# MotorController_ToniDove_Full04.net
KiCad netlist of a schematic drawn in EAGLE
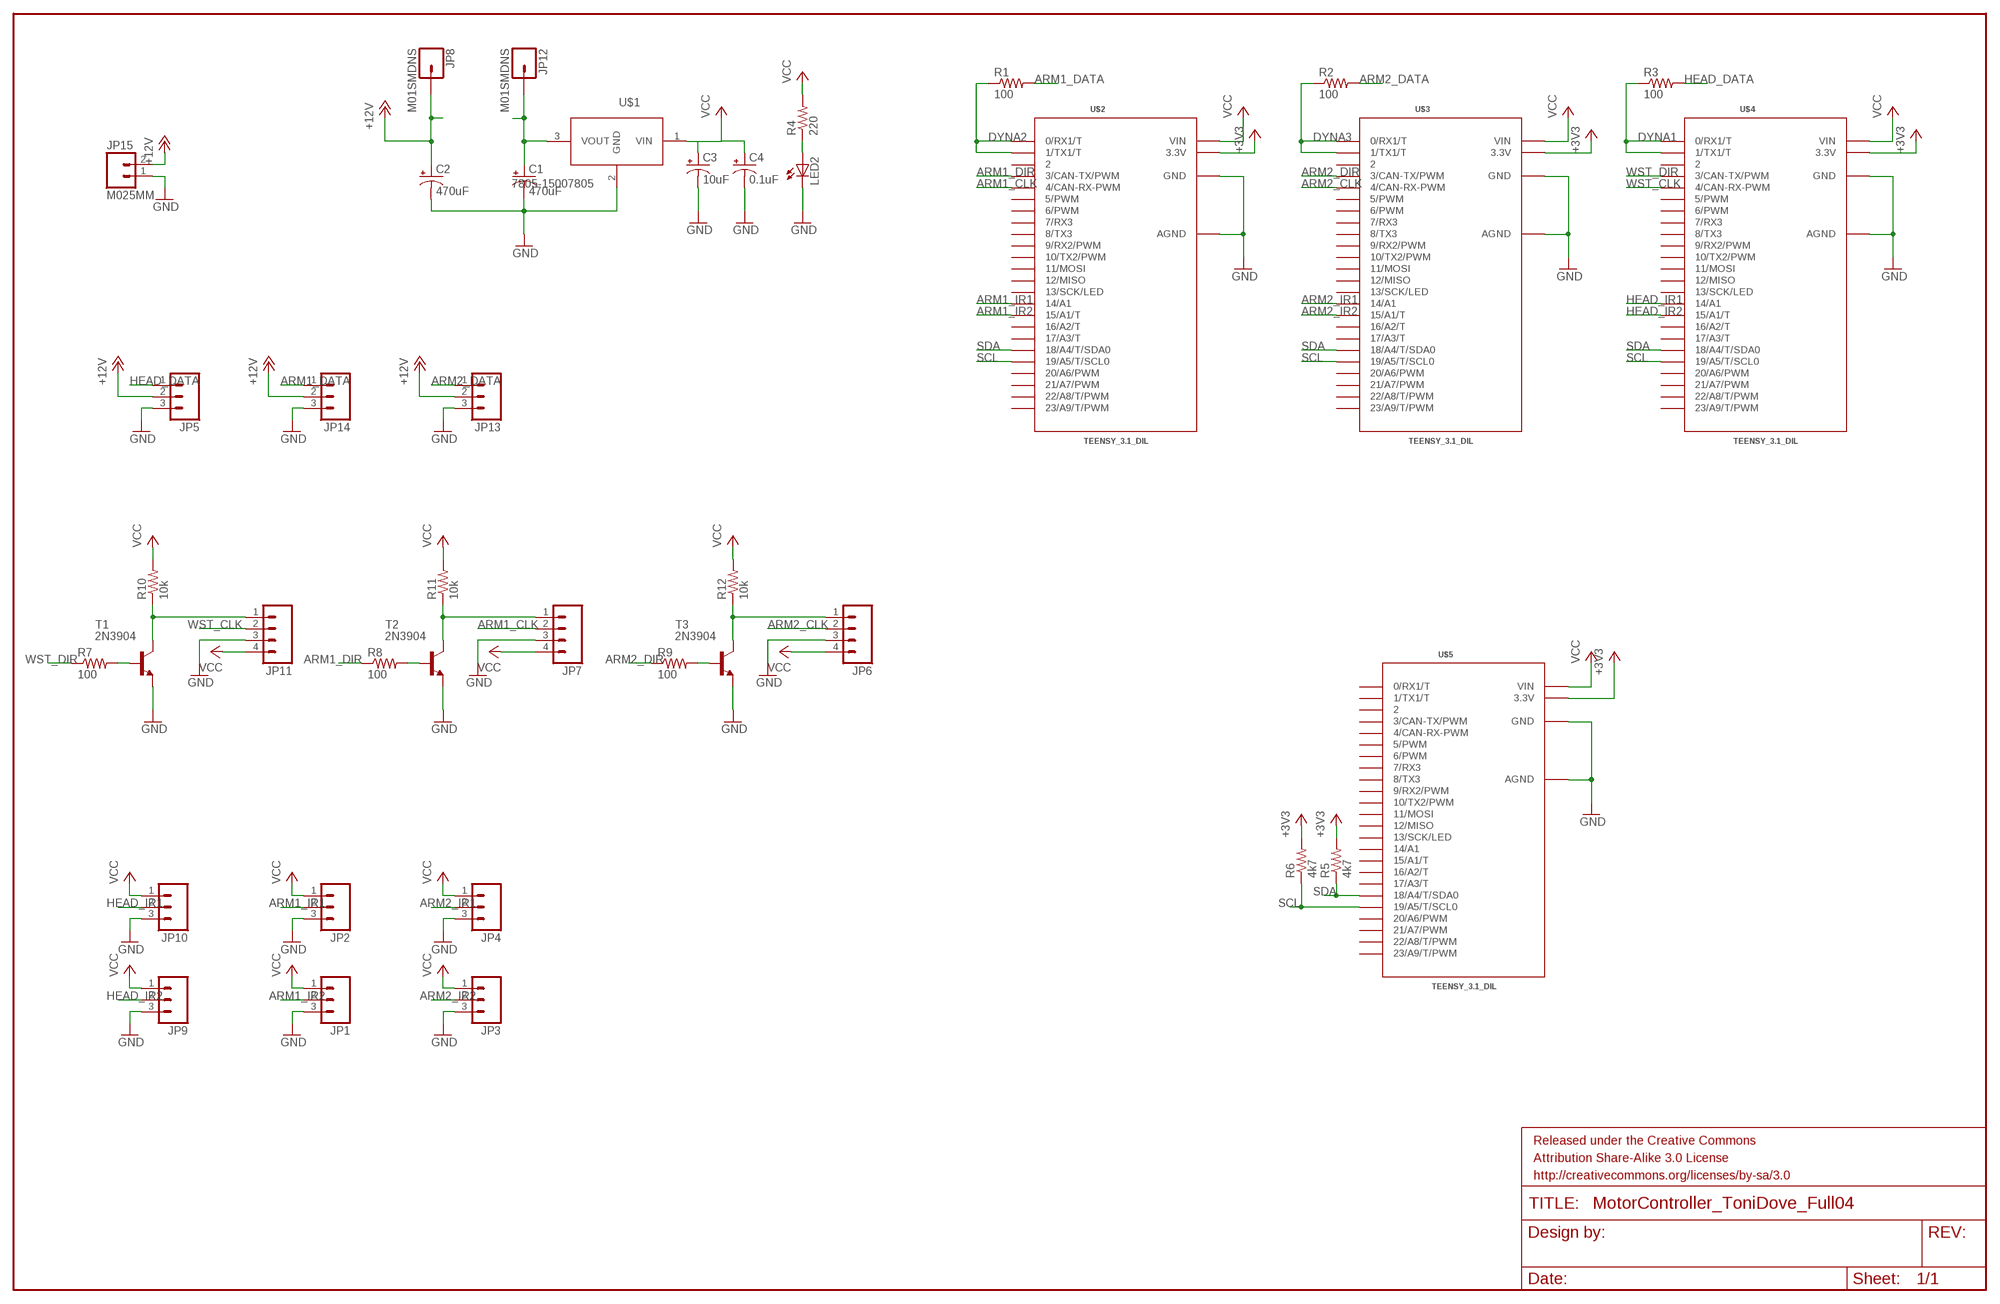
[diagram p0: schematic, sheet 1]

(export (version "E")
  (design (tool "Eeschema 10.0.6"))
  (components
    (comp (ref "C1")
      (value "470uF")
      (footprint "eagle-import:E5-13")
      (libsource (lib "eagle-import") (part "CPOL-USE5-13"))
    )
    (comp (ref "C2")
      (value "470uF")
      (footprint "eagle-import:E5-13")
      (libsource (lib "eagle-import") (part "CPOL-USE5-13"))
    )
    (comp (ref "C3")
      (value "10uF")
      (footprint "eagle-import:E2,5-6E")
      (libsource (lib "eagle-import") (part "CPOL-USE2,5-6E"))
    )
    (comp (ref "C4")
      (value "0.1uF")
      (footprint "eagle-import:E2,5-6E")
      (libsource (lib "eagle-import") (part "CPOL-USE2,5-6E"))
    )
    (comp (ref "FRAME1")
      (value "FRAME-LEDGER")
      (footprint "eagle-import:CREATIVE_COMMONS")
      (libsource (lib "eagle-import") (part "FRAME-LEDGER"))
    )
    (comp (ref "JP1")
      (value "M03PTH")
      (footprint "eagle-import:1X03")
      (libsource (lib "eagle-import") (part "M03PTH"))
    )
    (comp (ref "JP2")
      (value "M03PTH")
      (footprint "eagle-import:1X03")
      (libsource (lib "eagle-import") (part "M03PTH"))
    )
    (comp (ref "JP3")
      (value "M03PTH")
      (footprint "eagle-import:1X03")
      (libsource (lib "eagle-import") (part "M03PTH"))
    )
    (comp (ref "JP4")
      (value "M03PTH")
      (footprint "eagle-import:1X03")
      (libsource (lib "eagle-import") (part "M03PTH"))
    )
    (comp (ref "JP5")
      (value "M03PTH")
      (footprint "eagle-import:1X03")
      (libsource (lib "eagle-import") (part "M03PTH"))
    )
    (comp (ref "JP6")
      (value "M04SCREW")
      (footprint "eagle-import:SCREWTERMINAL-3.5MM-4")
      (libsource (lib "eagle-import") (part "M04SCREW"))
    )
    (comp (ref "JP7")
      (value "M04SCREW")
      (footprint "eagle-import:SCREWTERMINAL-3.5MM-4")
      (libsource (lib "eagle-import") (part "M04SCREW"))
    )
    (comp (ref "JP8")
      (value "M01SMDNS")
      (footprint "eagle-import:1X01NS")
      (libsource (lib "eagle-import") (part "M01SMDNS"))
    )
    (comp (ref "JP9")
      (value "M03PTH")
      (footprint "eagle-import:1X03")
      (libsource (lib "eagle-import") (part "M03PTH"))
    )
    (comp (ref "JP10")
      (value "M03PTH")
      (footprint "eagle-import:1X03")
      (libsource (lib "eagle-import") (part "M03PTH"))
    )
    (comp (ref "JP11")
      (value "M04SCREW")
      (footprint "eagle-import:SCREWTERMINAL-3.5MM-4")
      (libsource (lib "eagle-import") (part "M04SCREW"))
    )
    (comp (ref "JP12")
      (value "M01SMDNS")
      (footprint "eagle-import:1X01NS")
      (libsource (lib "eagle-import") (part "M01SMDNS"))
    )
    (comp (ref "JP13")
      (value "M03PTH")
      (footprint "eagle-import:1X03")
      (libsource (lib "eagle-import") (part "M03PTH"))
    )
    (comp (ref "JP14")
      (value "M03PTH")
      (footprint "eagle-import:1X03")
      (libsource (lib "eagle-import") (part "M03PTH"))
    )
    (comp (ref "JP15")
      (value "M025MM")
      (footprint "eagle-import:SCREWTERMINAL-5MM-2")
      (libsource (lib "eagle-import") (part "M025MM"))
    )
    (comp (ref "LED2")
      (value "LED5MM")
      (footprint "eagle-import:LED5MM")
      (libsource (lib "eagle-import") (part "LED5MM"))
    )
    (comp (ref "R1")
      (value "100")
      (footprint "eagle-import:0204_7")
      (libsource (lib "eagle-import") (part "R-US_0204/7"))
    )
    (comp (ref "R2")
      (value "100")
      (footprint "eagle-import:0204_7")
      (libsource (lib "eagle-import") (part "R-US_0204/7"))
    )
    (comp (ref "R3")
      (value "100")
      (footprint "eagle-import:0204_7")
      (libsource (lib "eagle-import") (part "R-US_0204/7"))
    )
    (comp (ref "R4")
      (value "220")
      (footprint "eagle-import:0204_7")
      (libsource (lib "eagle-import") (part "R-US_0204/7"))
    )
    (comp (ref "R5")
      (value "4k7")
      (footprint "eagle-import:0204_7")
      (libsource (lib "eagle-import") (part "R-US_0204/7"))
    )
    (comp (ref "R6")
      (value "4k7")
      (footprint "eagle-import:0204_7")
      (libsource (lib "eagle-import") (part "R-US_0204/7"))
    )
    (comp (ref "R7")
      (value "100")
      (footprint "eagle-import:0204_7")
      (libsource (lib "eagle-import") (part "R-US_0204/7"))
    )
    (comp (ref "R8")
      (value "100")
      (footprint "eagle-import:0204_7")
      (libsource (lib "eagle-import") (part "R-US_0204/7"))
    )
    (comp (ref "R9")
      (value "100")
      (footprint "eagle-import:0204_7")
      (libsource (lib "eagle-import") (part "R-US_0204/7"))
    )
    (comp (ref "R10")
      (value "10k")
      (footprint "eagle-import:0204_7")
      (libsource (lib "eagle-import") (part "R-US_0204/7"))
    )
    (comp (ref "R11")
      (value "10k")
      (footprint "eagle-import:0204_7")
      (libsource (lib "eagle-import") (part "R-US_0204/7"))
    )
    (comp (ref "R12")
      (value "10k")
      (footprint "eagle-import:0204_7")
      (libsource (lib "eagle-import") (part "R-US_0204/7"))
    )
    (comp (ref "T1")
      (value "2N3904")
      (footprint "eagle-import:TO92")
      (libsource (lib "eagle-import") (part "2N3904"))
    )
    (comp (ref "T2")
      (value "2N3904")
      (footprint "eagle-import:TO92")
      (libsource (lib "eagle-import") (part "2N3904"))
    )
    (comp (ref "T3")
      (value "2N3904")
      (footprint "eagle-import:TO92")
      (libsource (lib "eagle-import") (part "2N3904"))
    )
    (comp (ref "U$1")
      (value "7805-15007805")
      (footprint "eagle-import:UL94-V0")
      (libsource (lib "eagle-import") (part "7805-15007805"))
    )
    (comp (ref "U$2")
      (value "TEENSY_3.1_DIL")
      (footprint "eagle-import:TEENSY3-DIL")
      (libsource (lib "eagle-import") (part "TEENSY_3.1_DIL"))
    )
    (comp (ref "U$3")
      (value "TEENSY_3.1_DIL")
      (footprint "eagle-import:TEENSY3-DIL")
      (libsource (lib "eagle-import") (part "TEENSY_3.1_DIL"))
    )
    (comp (ref "U$4")
      (value "TEENSY_3.1_DIL")
      (footprint "eagle-import:TEENSY3-DIL")
      (libsource (lib "eagle-import") (part "TEENSY_3.1_DIL"))
    )
    (comp (ref "U$5")
      (value "TEENSY_3.1_DIL")
      (footprint "eagle-import:TEENSY3-DIL")
      (libsource (lib "eagle-import") (part "TEENSY_3.1_DIL"))
    )
  )
  (nets
    (net (code "1") (name "+3V3") (class "Default")
      (node (ref "R5") (pin "2") (pinfunction "2_2") (pintype "passive"))
      (node (ref "R6") (pin "2") (pinfunction "2_2") (pintype "passive"))
      (node (ref "U$2") (pin "3.3V") (pinfunction "3.3V_3.3V") (pintype "power_in"))
      (node (ref "U$3") (pin "3.3V") (pinfunction "3.3V_3.3V") (pintype "power_in"))
      (node (ref "U$4") (pin "3.3V") (pinfunction "3.3V_3.3V") (pintype "power_in"))
      (node (ref "U$5") (pin "3.3V") (pinfunction "3.3V_3.3V") (pintype "power_in"))
    )
    (net (code "2") (name "+12V") (class "Default")
      (node (ref "C2") (pin "+") (pinfunction "+_+") (pintype "passive"))
      (node (ref "JP13") (pin "2") (pinfunction "2_2") (pintype "passive"))
      (node (ref "JP14") (pin "2") (pinfunction "2_2") (pintype "passive"))
      (node (ref "JP15") (pin "2") (pinfunction "2_2") (pintype "passive"))
      (node (ref "JP5") (pin "2") (pinfunction "2_2") (pintype "passive"))
      (node (ref "JP8") (pin "1") (pinfunction "1_1") (pintype "passive"))
    )
    (net (code "3") (name "/ARM1_CLK") (class "Default")
      (node (ref "JP7") (pin "2") (pinfunction "2_2") (pintype "passive"))
      (node (ref "U$2") (pin "4") (pinfunction "4/CAN-RX-PWM_4") (pintype "bidirectional"))
    )
    (net (code "4") (name "/ARM1_DATA") (class "Default")
      (node (ref "JP14") (pin "1") (pinfunction "1_1") (pintype "passive"))
      (node (ref "R1") (pin "2") (pinfunction "2_2") (pintype "passive"))
    )
    (net (code "5") (name "/ARM1_DIR") (class "Default")
      (node (ref "R8") (pin "1") (pinfunction "1_1") (pintype "passive"))
      (node (ref "U$2") (pin "3") (pinfunction "3/CAN-TX/PWM_3") (pintype "bidirectional"))
    )
    (net (code "6") (name "/ARM1_IR1") (class "Default")
      (node (ref "JP2") (pin "2") (pinfunction "2_2") (pintype "passive"))
      (node (ref "U$2") (pin "14/A0") (pinfunction "14/A1_14/A0") (pintype "bidirectional"))
    )
    (net (code "7") (name "/ARM1_IR2") (class "Default")
      (node (ref "JP1") (pin "2") (pinfunction "2_2") (pintype "passive"))
      (node (ref "U$2") (pin "15/A1") (pinfunction "15/A1/T_15/A1") (pintype "bidirectional"))
    )
    (net (code "8") (name "/ARM2_CLK") (class "Default")
      (node (ref "JP6") (pin "2") (pinfunction "2_2") (pintype "passive"))
      (node (ref "U$3") (pin "4") (pinfunction "4/CAN-RX-PWM_4") (pintype "bidirectional"))
    )
    (net (code "9") (name "/ARM2_DATA") (class "Default")
      (node (ref "JP13") (pin "1") (pinfunction "1_1") (pintype "passive"))
      (node (ref "R2") (pin "2") (pinfunction "2_2") (pintype "passive"))
    )
    (net (code "10") (name "/ARM2_DIR") (class "Default")
      (node (ref "R9") (pin "1") (pinfunction "1_1") (pintype "passive"))
      (node (ref "U$3") (pin "3") (pinfunction "3/CAN-TX/PWM_3") (pintype "bidirectional"))
    )
    (net (code "11") (name "/ARM2_IR1") (class "Default")
      (node (ref "JP4") (pin "2") (pinfunction "2_2") (pintype "passive"))
      (node (ref "U$3") (pin "14/A0") (pinfunction "14/A1_14/A0") (pintype "bidirectional"))
    )
    (net (code "12") (name "/ARM2_IR2") (class "Default")
      (node (ref "JP3") (pin "2") (pinfunction "2_2") (pintype "passive"))
      (node (ref "U$3") (pin "15/A1") (pinfunction "15/A1/T_15/A1") (pintype "bidirectional"))
    )
    (net (code "13") (name "/DYNA1") (class "Default")
      (node (ref "R3") (pin "1") (pinfunction "1_1") (pintype "passive"))
      (node (ref "U$4") (pin "0") (pinfunction "0/RX1/T_0") (pintype "bidirectional"))
      (node (ref "U$4") (pin "1") (pinfunction "1/TX1/T_1") (pintype "bidirectional"))
    )
    (net (code "14") (name "/DYNA2") (class "Default")
      (node (ref "R1") (pin "1") (pinfunction "1_1") (pintype "passive"))
      (node (ref "U$2") (pin "0") (pinfunction "0/RX1/T_0") (pintype "bidirectional"))
      (node (ref "U$2") (pin "1") (pinfunction "1/TX1/T_1") (pintype "bidirectional"))
    )
    (net (code "15") (name "/DYNA3") (class "Default")
      (node (ref "R2") (pin "1") (pinfunction "1_1") (pintype "passive"))
      (node (ref "U$3") (pin "0") (pinfunction "0/RX1/T_0") (pintype "bidirectional"))
      (node (ref "U$3") (pin "1") (pinfunction "1/TX1/T_1") (pintype "bidirectional"))
    )
    (net (code "16") (name "/HEAD_DATA") (class "Default")
      (node (ref "JP5") (pin "1") (pinfunction "1_1") (pintype "passive"))
      (node (ref "R3") (pin "2") (pinfunction "2_2") (pintype "passive"))
    )
    (net (code "17") (name "/HEAD_IR1") (class "Default")
      (node (ref "JP10") (pin "2") (pinfunction "2_2") (pintype "passive"))
      (node (ref "U$4") (pin "14/A0") (pinfunction "14/A1_14/A0") (pintype "bidirectional"))
    )
    (net (code "18") (name "/HEAD_IR2") (class "Default")
      (node (ref "JP9") (pin "2") (pinfunction "2_2") (pintype "passive"))
      (node (ref "U$4") (pin "15/A1") (pinfunction "15/A1/T_15/A1") (pintype "bidirectional"))
    )
    (net (code "19") (name "/SCL") (class "Default")
      (node (ref "R6") (pin "1") (pinfunction "1_1") (pintype "passive"))
      (node (ref "U$2") (pin "19/A5") (pinfunction "19/A5/T/SCL0_19/A5") (pintype "bidirectional"))
      (node (ref "U$3") (pin "19/A5") (pinfunction "19/A5/T/SCL0_19/A5") (pintype "bidirectional"))
      (node (ref "U$4") (pin "19/A5") (pinfunction "19/A5/T/SCL0_19/A5") (pintype "bidirectional"))
      (node (ref "U$5") (pin "19/A5") (pinfunction "19/A5/T/SCL0_19/A5") (pintype "bidirectional"))
    )
    (net (code "20") (name "/SDA") (class "Default")
      (node (ref "R5") (pin "1") (pinfunction "1_1") (pintype "passive"))
      (node (ref "U$2") (pin "18/A4") (pinfunction "18/A4/T/SDA0_18/A4") (pintype "bidirectional"))
      (node (ref "U$3") (pin "18/A4") (pinfunction "18/A4/T/SDA0_18/A4") (pintype "bidirectional"))
      (node (ref "U$4") (pin "18/A4") (pinfunction "18/A4/T/SDA0_18/A4") (pintype "bidirectional"))
      (node (ref "U$5") (pin "18/A4") (pinfunction "18/A4/T/SDA0_18/A4") (pintype "bidirectional"))
    )
    (net (code "21") (name "/WST_CLK") (class "Default")
      (node (ref "JP11") (pin "2") (pinfunction "2_2") (pintype "passive"))
      (node (ref "U$4") (pin "4") (pinfunction "4/CAN-RX-PWM_4") (pintype "bidirectional"))
    )
    (net (code "22") (name "/WST_DIR") (class "Default")
      (node (ref "R7") (pin "1") (pinfunction "1_1") (pintype "passive"))
      (node (ref "U$4") (pin "3") (pinfunction "3/CAN-TX/PWM_3") (pintype "bidirectional"))
    )
    (net (code "23") (name "GND") (class "Default")
      (node (ref "C1") (pin "-") (pinfunction "-_-") (pintype "passive"))
      (node (ref "C2") (pin "-") (pinfunction "-_-") (pintype "passive"))
      (node (ref "C3") (pin "-") (pinfunction "-_-") (pintype "passive"))
      (node (ref "C4") (pin "-") (pinfunction "-_-") (pintype "passive"))
      (node (ref "JP1") (pin "3") (pinfunction "3_3") (pintype "passive"))
      (node (ref "JP10") (pin "3") (pinfunction "3_3") (pintype "passive"))
      (node (ref "JP11") (pin "3") (pinfunction "3_3") (pintype "passive"))
      (node (ref "JP13") (pin "3") (pinfunction "3_3") (pintype "passive"))
      (node (ref "JP14") (pin "3") (pinfunction "3_3") (pintype "passive"))
      (node (ref "JP15") (pin "1") (pinfunction "1_1") (pintype "passive"))
      (node (ref "JP2") (pin "3") (pinfunction "3_3") (pintype "passive"))
      (node (ref "JP3") (pin "3") (pinfunction "3_3") (pintype "passive"))
      (node (ref "JP4") (pin "3") (pinfunction "3_3") (pintype "passive"))
      (node (ref "JP5") (pin "3") (pinfunction "3_3") (pintype "passive"))
      (node (ref "JP6") (pin "3") (pinfunction "3_3") (pintype "passive"))
      (node (ref "JP7") (pin "3") (pinfunction "3_3") (pintype "passive"))
      (node (ref "JP9") (pin "3") (pinfunction "3_3") (pintype "passive"))
      (node (ref "LED2") (pin "K") (pinfunction "C_K") (pintype "passive"))
      (node (ref "T1") (pin "3") (pinfunction "E_3") (pintype "passive"))
      (node (ref "T2") (pin "3") (pinfunction "E_3") (pintype "passive"))
      (node (ref "T3") (pin "3") (pinfunction "E_3") (pintype "passive"))
      (node (ref "U$1") (pin "2") (pinfunction "GND_2") (pintype "bidirectional"))
      (node (ref "U$2") (pin "AGND") (pinfunction "AGND_AGND") (pintype "power_in"))
      (node (ref "U$2") (pin "GND") (pinfunction "GND_GND") (pintype "power_in"))
      (node (ref "U$3") (pin "AGND") (pinfunction "AGND_AGND") (pintype "power_in"))
      (node (ref "U$3") (pin "GND") (pinfunction "GND_GND") (pintype "power_in"))
      (node (ref "U$4") (pin "AGND") (pinfunction "AGND_AGND") (pintype "power_in"))
      (node (ref "U$4") (pin "GND") (pinfunction "GND_GND") (pintype "power_in"))
      (node (ref "U$5") (pin "AGND") (pinfunction "AGND_AGND") (pintype "power_in"))
      (node (ref "U$5") (pin "GND") (pinfunction "GND_GND") (pintype "power_in"))
    )
    (net (code "24") (name "Net-(LED2-PadA)") (class "Default")
      (node (ref "LED2") (pin "A") (pinfunction "A_A") (pintype "passive"))
      (node (ref "R4") (pin "1") (pinfunction "1_1") (pintype "passive"))
    )
    (net (code "25") (name "Net-(T1-B)") (class "Default")
      (node (ref "R7") (pin "2") (pinfunction "2_2") (pintype "passive"))
      (node (ref "T1") (pin "2") (pinfunction "B_2") (pintype "passive"))
    )
    (net (code "26") (name "Net-(T1-C)") (class "Default")
      (node (ref "JP11") (pin "1") (pinfunction "1_1") (pintype "passive"))
      (node (ref "R10") (pin "1") (pinfunction "1_1") (pintype "passive"))
      (node (ref "T1") (pin "1") (pinfunction "C_1") (pintype "passive"))
    )
    (net (code "27") (name "Net-(T2-B)") (class "Default")
      (node (ref "R8") (pin "2") (pinfunction "2_2") (pintype "passive"))
      (node (ref "T2") (pin "2") (pinfunction "B_2") (pintype "passive"))
    )
    (net (code "28") (name "Net-(T2-C)") (class "Default")
      (node (ref "JP7") (pin "1") (pinfunction "1_1") (pintype "passive"))
      (node (ref "R11") (pin "1") (pinfunction "1_1") (pintype "passive"))
      (node (ref "T2") (pin "1") (pinfunction "C_1") (pintype "passive"))
    )
    (net (code "29") (name "Net-(T3-B)") (class "Default")
      (node (ref "R9") (pin "2") (pinfunction "2_2") (pintype "passive"))
      (node (ref "T3") (pin "2") (pinfunction "B_2") (pintype "passive"))
    )
    (net (code "30") (name "Net-(T3-C)") (class "Default")
      (node (ref "JP6") (pin "1") (pinfunction "1_1") (pintype "passive"))
      (node (ref "R12") (pin "1") (pinfunction "1_1") (pintype "passive"))
      (node (ref "T3") (pin "1") (pinfunction "C_1") (pintype "passive"))
    )
    (net (code "31") (name "Net-(U$1-VOUT)") (class "Default")
      (node (ref "C1") (pin "+") (pinfunction "+_+") (pintype "passive"))
      (node (ref "JP12") (pin "1") (pinfunction "1_1") (pintype "passive"))
      (node (ref "U$1") (pin "3") (pinfunction "VOUT_3") (pintype "bidirectional"))
    )
    (net (code "32") (name "VCC") (class "Default")
      (node (ref "C3") (pin "+") (pinfunction "+_+") (pintype "passive"))
      (node (ref "C4") (pin "+") (pinfunction "+_+") (pintype "passive"))
      (node (ref "JP1") (pin "1") (pinfunction "1_1") (pintype "passive"))
      (node (ref "JP10") (pin "1") (pinfunction "1_1") (pintype "passive"))
      (node (ref "JP11") (pin "4") (pinfunction "4_4") (pintype "passive"))
      (node (ref "JP2") (pin "1") (pinfunction "1_1") (pintype "passive"))
      (node (ref "JP3") (pin "1") (pinfunction "1_1") (pintype "passive"))
      (node (ref "JP4") (pin "1") (pinfunction "1_1") (pintype "passive"))
      (node (ref "JP6") (pin "4") (pinfunction "4_4") (pintype "passive"))
      (node (ref "JP7") (pin "4") (pinfunction "4_4") (pintype "passive"))
      (node (ref "JP9") (pin "1") (pinfunction "1_1") (pintype "passive"))
      (node (ref "R10") (pin "2") (pinfunction "2_2") (pintype "passive"))
      (node (ref "R11") (pin "2") (pinfunction "2_2") (pintype "passive"))
      (node (ref "R12") (pin "2") (pinfunction "2_2") (pintype "passive"))
      (node (ref "R4") (pin "2") (pinfunction "2_2") (pintype "passive"))
      (node (ref "U$1") (pin "1") (pinfunction "VIN_1") (pintype "bidirectional"))
      (node (ref "U$2") (pin "VIN") (pinfunction "VIN_VIN") (pintype "power_in"))
      (node (ref "U$3") (pin "VIN") (pinfunction "VIN_VIN") (pintype "power_in"))
      (node (ref "U$4") (pin "VIN") (pinfunction "VIN_VIN") (pintype "power_in"))
      (node (ref "U$5") (pin "VIN") (pinfunction "VIN_VIN") (pintype "power_in"))
    )
    (net (code "33") (name "unconnected-(U$2-5{slash}PWM-Pad5)") (class "Default")
      (node (ref "U$2") (pin "5") (pinfunction "5/PWM_5") (pintype "bidirectional"))
    )
    (net (code "34") (name "unconnected-(U$2-6{slash}PWM-Pad6)") (class "Default")
      (node (ref "U$2") (pin "6") (pinfunction "6/PWM_6") (pintype "bidirectional"))
    )
    (net (code "35") (name "unconnected-(U$2-7{slash}RX3-Pad7)") (class "Default")
      (node (ref "U$2") (pin "7") (pinfunction "7/RX3_7") (pintype "bidirectional"))
    )
    (net (code "36") (name "unconnected-(U$2-8{slash}TX3-Pad8)") (class "Default")
      (node (ref "U$2") (pin "8") (pinfunction "8/TX3_8") (pintype "bidirectional"))
    )
    (net (code "37") (name "unconnected-(U$2-9{slash}RX2{slash}PWM-Pad9)") (class "Default")
      (node (ref "U$2") (pin "9") (pinfunction "9/RX2/PWM_9") (pintype "bidirectional"))
    )
    (net (code "38") (name "unconnected-(U$2-10{slash}TX2{slash}PWM-Pad10)") (class "Default")
      (node (ref "U$2") (pin "10") (pinfunction "10/TX2/PWM_10") (pintype "bidirectional"))
    )
    (net (code "39") (name "unconnected-(U$2-11{slash}MOSI-Pad11)") (class "Default")
      (node (ref "U$2") (pin "11") (pinfunction "11/MOSI_11") (pintype "bidirectional"))
    )
    (net (code "40") (name "unconnected-(U$2-12{slash}MISO-Pad12)") (class "Default")
      (node (ref "U$2") (pin "12") (pinfunction "12/MISO_12") (pintype "bidirectional"))
    )
    (net (code "41") (name "unconnected-(U$2-13{slash}SCK{slash}LED-Pad13)") (class "Default")
      (node (ref "U$2") (pin "13") (pinfunction "13/SCK/LED_13") (pintype "bidirectional"))
    )
    (net (code "42") (name "unconnected-(U$2-16{slash}A2{slash}T-Pad16{slash}A2)") (class "Default")
      (node (ref "U$2") (pin "16/A2") (pinfunction "16/A2/T_16/A2") (pintype "bidirectional"))
    )
    (net (code "43") (name "unconnected-(U$2-17{slash}A3{slash}T-Pad17{slash}A3)") (class "Default")
      (node (ref "U$2") (pin "17/A3") (pinfunction "17/A3/T_17/A3") (pintype "bidirectional"))
    )
    (net (code "44") (name "unconnected-(U$2-20{slash}A6{slash}PWM-Pad20{slash}A6)") (class "Default")
      (node (ref "U$2") (pin "20/A6") (pinfunction "20/A6/PWM_20/A6") (pintype "bidirectional"))
    )
    (net (code "45") (name "unconnected-(U$2-21{slash}A7{slash}PWM-Pad21{slash}A7)") (class "Default")
      (node (ref "U$2") (pin "21/A7") (pinfunction "21/A7/PWM_21/A7") (pintype "bidirectional"))
    )
    (net (code "46") (name "unconnected-(U$2-22{slash}A8{slash}T{slash}PWM-Pad22{slash}A8)") (class "Default")
      (node (ref "U$2") (pin "22/A8") (pinfunction "22/A8/T/PWM_22/A8") (pintype "bidirectional"))
    )
    (net (code "47") (name "unconnected-(U$2-23{slash}A9{slash}T{slash}PWM-Pad23{slash}A9)") (class "Default")
      (node (ref "U$2") (pin "23/A9") (pinfunction "23/A9/T/PWM_23/A9") (pintype "bidirectional"))
    )
    (net (code "48") (name "unconnected-(U$2-Pad2)") (class "Default")
      (node (ref "U$2") (pin "2") (pinfunction "2_2") (pintype "bidirectional"))
    )
    (net (code "49") (name "unconnected-(U$3-5{slash}PWM-Pad5)") (class "Default")
      (node (ref "U$3") (pin "5") (pinfunction "5/PWM_5") (pintype "bidirectional"))
    )
    (net (code "50") (name "unconnected-(U$3-6{slash}PWM-Pad6)") (class "Default")
      (node (ref "U$3") (pin "6") (pinfunction "6/PWM_6") (pintype "bidirectional"))
    )
    (net (code "51") (name "unconnected-(U$3-7{slash}RX3-Pad7)") (class "Default")
      (node (ref "U$3") (pin "7") (pinfunction "7/RX3_7") (pintype "bidirectional"))
    )
    (net (code "52") (name "unconnected-(U$3-8{slash}TX3-Pad8)") (class "Default")
      (node (ref "U$3") (pin "8") (pinfunction "8/TX3_8") (pintype "bidirectional"))
    )
    (net (code "53") (name "unconnected-(U$3-9{slash}RX2{slash}PWM-Pad9)") (class "Default")
      (node (ref "U$3") (pin "9") (pinfunction "9/RX2/PWM_9") (pintype "bidirectional"))
    )
    (net (code "54") (name "unconnected-(U$3-10{slash}TX2{slash}PWM-Pad10)") (class "Default")
      (node (ref "U$3") (pin "10") (pinfunction "10/TX2/PWM_10") (pintype "bidirectional"))
    )
    (net (code "55") (name "unconnected-(U$3-11{slash}MOSI-Pad11)") (class "Default")
      (node (ref "U$3") (pin "11") (pinfunction "11/MOSI_11") (pintype "bidirectional"))
    )
    (net (code "56") (name "unconnected-(U$3-12{slash}MISO-Pad12)") (class "Default")
      (node (ref "U$3") (pin "12") (pinfunction "12/MISO_12") (pintype "bidirectional"))
    )
    (net (code "57") (name "unconnected-(U$3-13{slash}SCK{slash}LED-Pad13)") (class "Default")
      (node (ref "U$3") (pin "13") (pinfunction "13/SCK/LED_13") (pintype "bidirectional"))
    )
    (net (code "58") (name "unconnected-(U$3-16{slash}A2{slash}T-Pad16{slash}A2)") (class "Default")
      (node (ref "U$3") (pin "16/A2") (pinfunction "16/A2/T_16/A2") (pintype "bidirectional"))
    )
    (net (code "59") (name "unconnected-(U$3-17{slash}A3{slash}T-Pad17{slash}A3)") (class "Default")
      (node (ref "U$3") (pin "17/A3") (pinfunction "17/A3/T_17/A3") (pintype "bidirectional"))
    )
    (net (code "60") (name "unconnected-(U$3-20{slash}A6{slash}PWM-Pad20{slash}A6)") (class "Default")
      (node (ref "U$3") (pin "20/A6") (pinfunction "20/A6/PWM_20/A6") (pintype "bidirectional"))
    )
    (net (code "61") (name "unconnected-(U$3-21{slash}A7{slash}PWM-Pad21{slash}A7)") (class "Default")
      (node (ref "U$3") (pin "21/A7") (pinfunction "21/A7/PWM_21/A7") (pintype "bidirectional"))
    )
    (net (code "62") (name "unconnected-(U$3-22{slash}A8{slash}T{slash}PWM-Pad22{slash}A8)") (class "Default")
      (node (ref "U$3") (pin "22/A8") (pinfunction "22/A8/T/PWM_22/A8") (pintype "bidirectional"))
    )
    (net (code "63") (name "unconnected-(U$3-23{slash}A9{slash}T{slash}PWM-Pad23{slash}A9)") (class "Default")
      (node (ref "U$3") (pin "23/A9") (pinfunction "23/A9/T/PWM_23/A9") (pintype "bidirectional"))
    )
    (net (code "64") (name "unconnected-(U$3-Pad2)") (class "Default")
      (node (ref "U$3") (pin "2") (pinfunction "2_2") (pintype "bidirectional"))
    )
    (net (code "65") (name "unconnected-(U$4-5{slash}PWM-Pad5)") (class "Default")
      (node (ref "U$4") (pin "5") (pinfunction "5/PWM_5") (pintype "bidirectional"))
    )
    (net (code "66") (name "unconnected-(U$4-6{slash}PWM-Pad6)") (class "Default")
      (node (ref "U$4") (pin "6") (pinfunction "6/PWM_6") (pintype "bidirectional"))
    )
    (net (code "67") (name "unconnected-(U$4-7{slash}RX3-Pad7)") (class "Default")
      (node (ref "U$4") (pin "7") (pinfunction "7/RX3_7") (pintype "bidirectional"))
    )
    (net (code "68") (name "unconnected-(U$4-8{slash}TX3-Pad8)") (class "Default")
      (node (ref "U$4") (pin "8") (pinfunction "8/TX3_8") (pintype "bidirectional"))
    )
    (net (code "69") (name "unconnected-(U$4-9{slash}RX2{slash}PWM-Pad9)") (class "Default")
      (node (ref "U$4") (pin "9") (pinfunction "9/RX2/PWM_9") (pintype "bidirectional"))
    )
    (net (code "70") (name "unconnected-(U$4-10{slash}TX2{slash}PWM-Pad10)") (class "Default")
      (node (ref "U$4") (pin "10") (pinfunction "10/TX2/PWM_10") (pintype "bidirectional"))
    )
    (net (code "71") (name "unconnected-(U$4-11{slash}MOSI-Pad11)") (class "Default")
      (node (ref "U$4") (pin "11") (pinfunction "11/MOSI_11") (pintype "bidirectional"))
    )
    (net (code "72") (name "unconnected-(U$4-12{slash}MISO-Pad12)") (class "Default")
      (node (ref "U$4") (pin "12") (pinfunction "12/MISO_12") (pintype "bidirectional"))
    )
    (net (code "73") (name "unconnected-(U$4-13{slash}SCK{slash}LED-Pad13)") (class "Default")
      (node (ref "U$4") (pin "13") (pinfunction "13/SCK/LED_13") (pintype "bidirectional"))
    )
    (net (code "74") (name "unconnected-(U$4-16{slash}A2{slash}T-Pad16{slash}A2)") (class "Default")
      (node (ref "U$4") (pin "16/A2") (pinfunction "16/A2/T_16/A2") (pintype "bidirectional"))
    )
    (net (code "75") (name "unconnected-(U$4-17{slash}A3{slash}T-Pad17{slash}A3)") (class "Default")
      (node (ref "U$4") (pin "17/A3") (pinfunction "17/A3/T_17/A3") (pintype "bidirectional"))
    )
    (net (code "76") (name "unconnected-(U$4-20{slash}A6{slash}PWM-Pad20{slash}A6)") (class "Default")
      (node (ref "U$4") (pin "20/A6") (pinfunction "20/A6/PWM_20/A6") (pintype "bidirectional"))
    )
    (net (code "77") (name "unconnected-(U$4-21{slash}A7{slash}PWM-Pad21{slash}A7)") (class "Default")
      (node (ref "U$4") (pin "21/A7") (pinfunction "21/A7/PWM_21/A7") (pintype "bidirectional"))
    )
    (net (code "78") (name "unconnected-(U$4-22{slash}A8{slash}T{slash}PWM-Pad22{slash}A8)") (class "Default")
      (node (ref "U$4") (pin "22/A8") (pinfunction "22/A8/T/PWM_22/A8") (pintype "bidirectional"))
    )
    (net (code "79") (name "unconnected-(U$4-23{slash}A9{slash}T{slash}PWM-Pad23{slash}A9)") (class "Default")
      (node (ref "U$4") (pin "23/A9") (pinfunction "23/A9/T/PWM_23/A9") (pintype "bidirectional"))
    )
    (net (code "80") (name "unconnected-(U$4-Pad2)") (class "Default")
      (node (ref "U$4") (pin "2") (pinfunction "2_2") (pintype "bidirectional"))
    )
    (net (code "81") (name "unconnected-(U$5-0{slash}RX1{slash}T-Pad0)") (class "Default")
      (node (ref "U$5") (pin "0") (pinfunction "0/RX1/T_0") (pintype "bidirectional"))
    )
    (net (code "82") (name "unconnected-(U$5-1{slash}TX1{slash}T-Pad1)") (class "Default")
      (node (ref "U$5") (pin "1") (pinfunction "1/TX1/T_1") (pintype "bidirectional"))
    )
    (net (code "83") (name "unconnected-(U$5-3{slash}CAN-TX{slash}PWM-Pad3)") (class "Default")
      (node (ref "U$5") (pin "3") (pinfunction "3/CAN-TX/PWM_3") (pintype "bidirectional"))
    )
    (net (code "84") (name "unconnected-(U$5-4{slash}CAN-RX-PWM-Pad4)") (class "Default")
      (node (ref "U$5") (pin "4") (pinfunction "4/CAN-RX-PWM_4") (pintype "bidirectional"))
    )
    (net (code "85") (name "unconnected-(U$5-5{slash}PWM-Pad5)") (class "Default")
      (node (ref "U$5") (pin "5") (pinfunction "5/PWM_5") (pintype "bidirectional"))
    )
    (net (code "86") (name "unconnected-(U$5-6{slash}PWM-Pad6)") (class "Default")
      (node (ref "U$5") (pin "6") (pinfunction "6/PWM_6") (pintype "bidirectional"))
    )
    (net (code "87") (name "unconnected-(U$5-7{slash}RX3-Pad7)") (class "Default")
      (node (ref "U$5") (pin "7") (pinfunction "7/RX3_7") (pintype "bidirectional"))
    )
    (net (code "88") (name "unconnected-(U$5-8{slash}TX3-Pad8)") (class "Default")
      (node (ref "U$5") (pin "8") (pinfunction "8/TX3_8") (pintype "bidirectional"))
    )
    (net (code "89") (name "unconnected-(U$5-9{slash}RX2{slash}PWM-Pad9)") (class "Default")
      (node (ref "U$5") (pin "9") (pinfunction "9/RX2/PWM_9") (pintype "bidirectional"))
    )
    (net (code "90") (name "unconnected-(U$5-10{slash}TX2{slash}PWM-Pad10)") (class "Default")
      (node (ref "U$5") (pin "10") (pinfunction "10/TX2/PWM_10") (pintype "bidirectional"))
    )
    (net (code "91") (name "unconnected-(U$5-11{slash}MOSI-Pad11)") (class "Default")
      (node (ref "U$5") (pin "11") (pinfunction "11/MOSI_11") (pintype "bidirectional"))
    )
    (net (code "92") (name "unconnected-(U$5-12{slash}MISO-Pad12)") (class "Default")
      (node (ref "U$5") (pin "12") (pinfunction "12/MISO_12") (pintype "bidirectional"))
    )
    (net (code "93") (name "unconnected-(U$5-13{slash}SCK{slash}LED-Pad13)") (class "Default")
      (node (ref "U$5") (pin "13") (pinfunction "13/SCK/LED_13") (pintype "bidirectional"))
    )
    (net (code "94") (name "unconnected-(U$5-14{slash}A1-Pad14{slash}A0)") (class "Default")
      (node (ref "U$5") (pin "14/A0") (pinfunction "14/A1_14/A0") (pintype "bidirectional"))
    )
    (net (code "95") (name "unconnected-(U$5-15{slash}A1{slash}T-Pad15{slash}A1)") (class "Default")
      (node (ref "U$5") (pin "15/A1") (pinfunction "15/A1/T_15/A1") (pintype "bidirectional"))
    )
    (net (code "96") (name "unconnected-(U$5-16{slash}A2{slash}T-Pad16{slash}A2)") (class "Default")
      (node (ref "U$5") (pin "16/A2") (pinfunction "16/A2/T_16/A2") (pintype "bidirectional"))
    )
    (net (code "97") (name "unconnected-(U$5-17{slash}A3{slash}T-Pad17{slash}A3)") (class "Default")
      (node (ref "U$5") (pin "17/A3") (pinfunction "17/A3/T_17/A3") (pintype "bidirectional"))
    )
    (net (code "98") (name "unconnected-(U$5-20{slash}A6{slash}PWM-Pad20{slash}A6)") (class "Default")
      (node (ref "U$5") (pin "20/A6") (pinfunction "20/A6/PWM_20/A6") (pintype "bidirectional"))
    )
    (net (code "99") (name "unconnected-(U$5-21{slash}A7{slash}PWM-Pad21{slash}A7)") (class "Default")
      (node (ref "U$5") (pin "21/A7") (pinfunction "21/A7/PWM_21/A7") (pintype "bidirectional"))
    )
    (net (code "100") (name "unconnected-(U$5-22{slash}A8{slash}T{slash}PWM-Pad22{slash}A8)") (class "Default")
      (node (ref "U$5") (pin "22/A8") (pinfunction "22/A8/T/PWM_22/A8") (pintype "bidirectional"))
    )
    (net (code "101") (name "unconnected-(U$5-23{slash}A9{slash}T{slash}PWM-Pad23{slash}A9)") (class "Default")
      (node (ref "U$5") (pin "23/A9") (pinfunction "23/A9/T/PWM_23/A9") (pintype "bidirectional"))
    )
    (net (code "102") (name "unconnected-(U$5-Pad2)") (class "Default")
      (node (ref "U$5") (pin "2") (pinfunction "2_2") (pintype "bidirectional"))
    )
  )
)
